# M242A.net
KiCad netlist of a schematic drawn in EAGLE
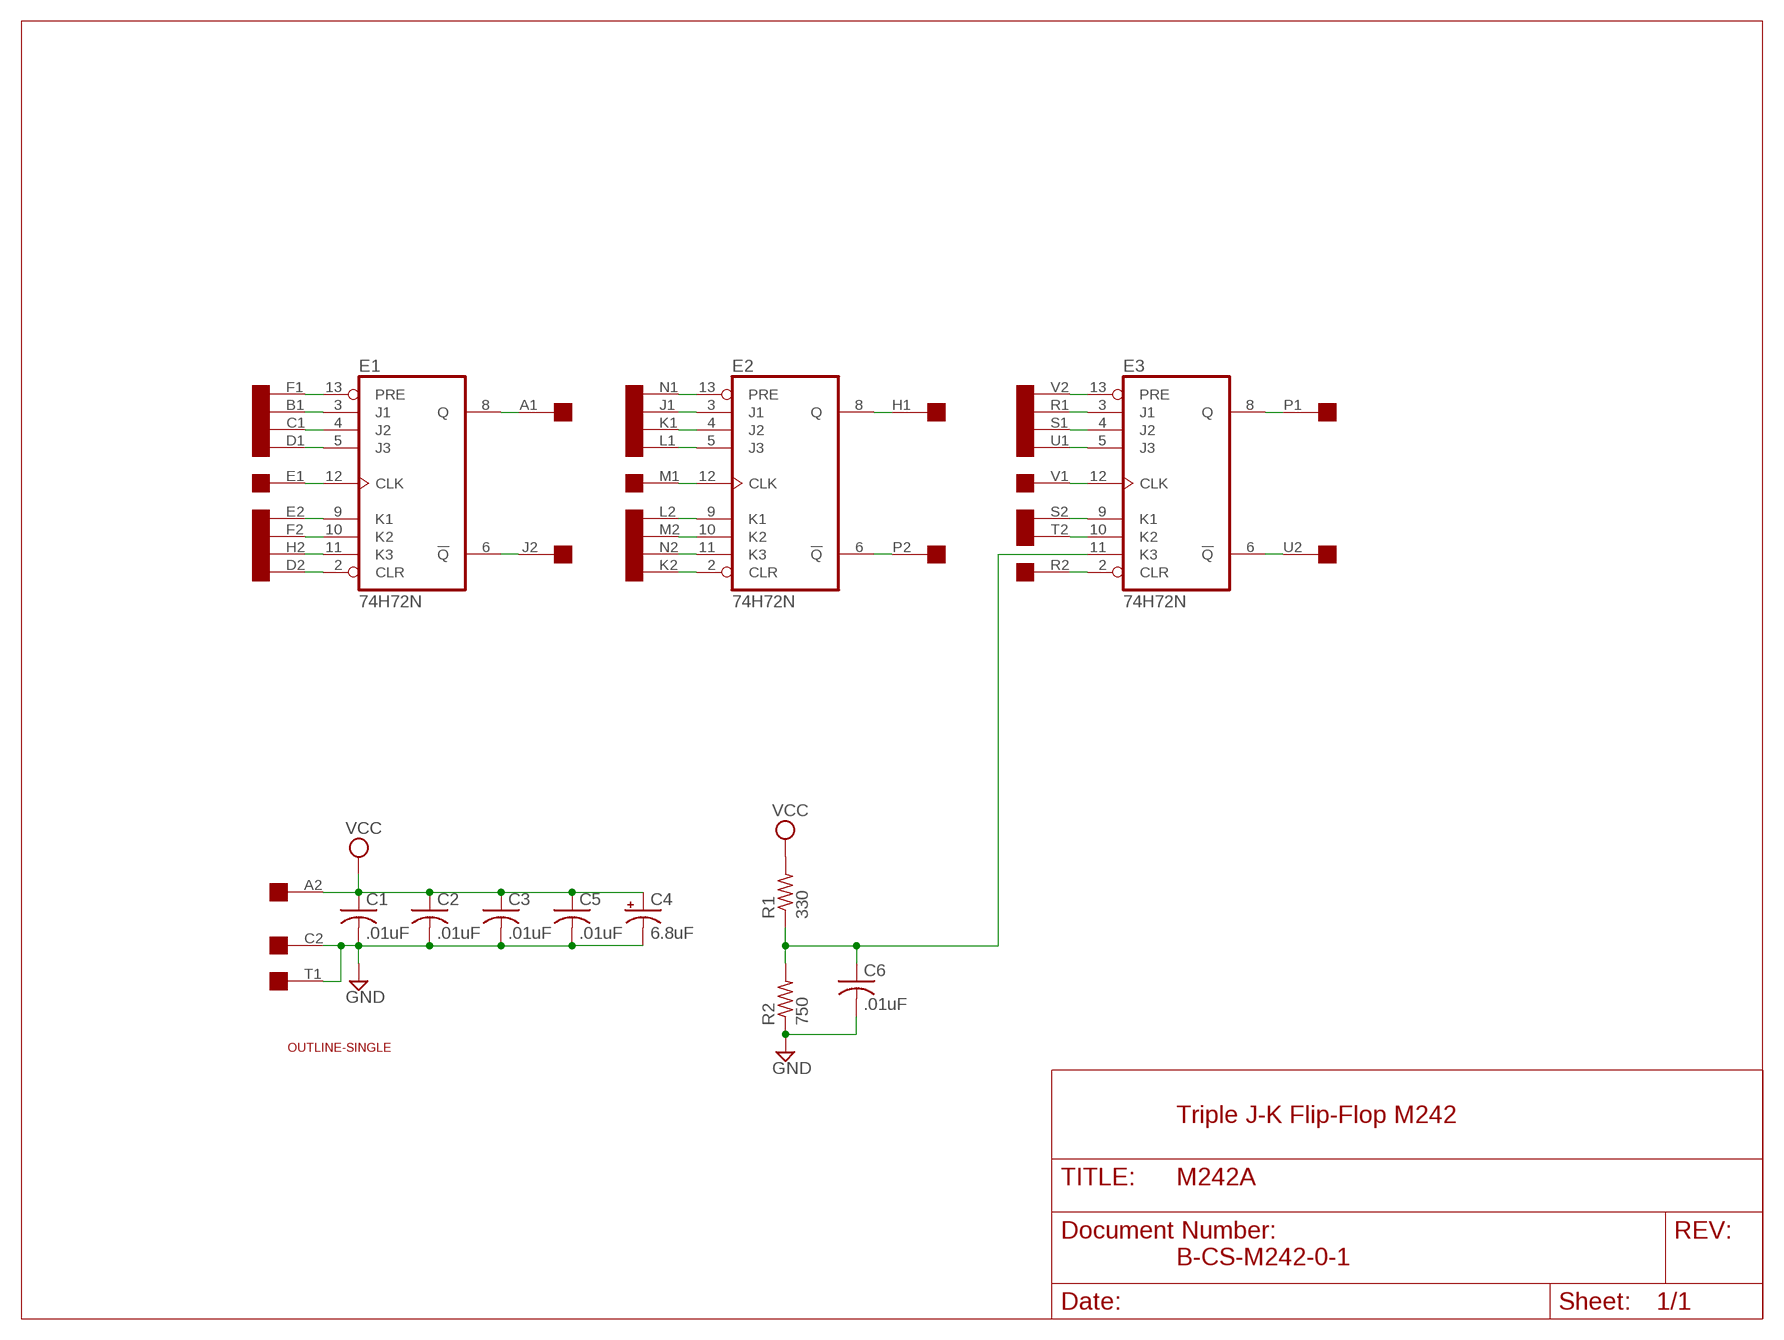
[diagram p0: schematic, sheet 1]

(export (version "E")
  (design (tool "Eeschema 10.0.6"))
  (components
    (comp (ref "C1")
      (value ".01uF")
      (footprint "eagle-import:C050-025X075")
      (libsource (lib "eagle-import") (part "C-US050-025X075"))
    )
    (comp (ref "C2")
      (value ".01uF")
      (footprint "eagle-import:C050-025X075")
      (libsource (lib "eagle-import") (part "C-US050-025X075"))
    )
    (comp (ref "C3")
      (value ".01uF")
      (footprint "eagle-import:C050-025X075")
      (libsource (lib "eagle-import") (part "C-US050-025X075"))
    )
    (comp (ref "C4")
      (value "6.8uF")
      (footprint "eagle-import:E12-8")
      (libsource (lib "eagle-import") (part "CPOL-USE20-8AXIAL"))
    )
    (comp (ref "C5")
      (value ".01uF")
      (footprint "eagle-import:C050-025X075")
      (libsource (lib "eagle-import") (part "C-US050-025X075"))
    )
    (comp (ref "C6")
      (value ".01uF")
      (footprint "eagle-import:C050-025X075")
      (libsource (lib "eagle-import") (part "C-US050-025X075"))
    )
    (comp (ref "E1")
      (value "74H72N")
      (footprint "eagle-import:DIL14")
      (libsource (lib "eagle-import") (part "7472N"))
    )
    (comp (ref "E2")
      (value "74H72N")
      (footprint "eagle-import:DIL14")
      (libsource (lib "eagle-import") (part "7472N"))
    )
    (comp (ref "E3")
      (value "74H72N")
      (footprint "eagle-import:DIL14")
      (libsource (lib "eagle-import") (part "7472N"))
    )
    (comp (ref "R1")
      (value "330")
      (footprint "eagle-import:0207_10")
      (libsource (lib "eagle-import") (part "R-US_0207/10"))
    )
    (comp (ref "R2")
      (value "750")
      (footprint "eagle-import:0207_10")
      (libsource (lib "eagle-import") (part "R-US_0207/10"))
    )
    (comp (ref "U$1")
      (value "OUTLINE-SINGLE")
      (footprint "eagle-import:SINGLE")
      (libsource (lib "eagle-import") (part "OUTLINE-SINGLE"))
    )
    (comp (ref "U$2")
      (value "SINGLE")
      (footprint "eagle-import:EDGE-CON2")
      (libsource (lib "eagle-import") (part "SINGLE"))
    )
  )
  (nets
    (net (code "1") (name "GND") (class "Default")
      (node (ref "C1") (pin "2") (pinfunction "2_2") (pintype "passive"))
      (node (ref "C2") (pin "2") (pinfunction "2_2") (pintype "passive"))
      (node (ref "C3") (pin "2") (pinfunction "2_2") (pintype "passive"))
      (node (ref "C4") (pin "-") (pinfunction "-_-") (pintype "passive"))
      (node (ref "C5") (pin "2") (pinfunction "2_2") (pintype "passive"))
      (node (ref "C6") (pin "2") (pinfunction "2_2") (pintype "passive"))
      (node (ref "R2") (pin "1") (pinfunction "1_1") (pintype "passive"))
      (node (ref "U$2") (pin "C2") (pinfunction "1_C2") (pintype "bidirectional"))
      (node (ref "U$2") (pin "T1") (pinfunction "1_T1") (pintype "bidirectional"))
    )
    (net (code "2") (name "Net-(E1A-CLK)") (class "Default")
      (node (ref "E1") (pin "12") (pinfunction "CLK_12") (pintype "input"))
      (node (ref "U$2") (pin "E1") (pinfunction "1_E1") (pintype "bidirectional"))
    )
    (net (code "3") (name "Net-(E1A-CLR)") (class "Default")
      (node (ref "E1") (pin "2") (pinfunction "CLR_2") (pintype "input"))
      (node (ref "U$2") (pin "D2") (pinfunction "1_D2") (pintype "bidirectional"))
    )
    (net (code "4") (name "Net-(E1A-J1)") (class "Default")
      (node (ref "E1") (pin "3") (pinfunction "J1_3") (pintype "input"))
      (node (ref "U$2") (pin "B1") (pinfunction "1_B1") (pintype "bidirectional"))
    )
    (net (code "5") (name "Net-(E1A-J2)") (class "Default")
      (node (ref "E1") (pin "4") (pinfunction "J2_4") (pintype "input"))
      (node (ref "U$2") (pin "C1") (pinfunction "1_C1") (pintype "bidirectional"))
    )
    (net (code "6") (name "Net-(E1A-J3)") (class "Default")
      (node (ref "E1") (pin "5") (pinfunction "J3_5") (pintype "input"))
      (node (ref "U$2") (pin "D1") (pinfunction "1_D1") (pintype "bidirectional"))
    )
    (net (code "7") (name "Net-(E1A-K1)") (class "Default")
      (node (ref "E1") (pin "9") (pinfunction "K1_9") (pintype "input"))
      (node (ref "U$2") (pin "E2") (pinfunction "1_E2") (pintype "bidirectional"))
    )
    (net (code "8") (name "Net-(E1A-K2)") (class "Default")
      (node (ref "E1") (pin "10") (pinfunction "K2_10") (pintype "input"))
      (node (ref "U$2") (pin "F2") (pinfunction "1_F2") (pintype "bidirectional"))
    )
    (net (code "9") (name "Net-(E1A-K3)") (class "Default")
      (node (ref "E1") (pin "11") (pinfunction "K3_11") (pintype "input"))
      (node (ref "U$2") (pin "H2") (pinfunction "1_H2") (pintype "bidirectional"))
    )
    (net (code "10") (name "Net-(E1A-PRE)") (class "Default")
      (node (ref "E1") (pin "13") (pinfunction "PRE_13") (pintype "input"))
      (node (ref "U$2") (pin "F1") (pinfunction "1_F1") (pintype "bidirectional"))
    )
    (net (code "11") (name "Net-(E1A-Q)") (class "Default")
      (node (ref "E1") (pin "8") (pinfunction "Q_8") (pintype "output"))
      (node (ref "U$2") (pin "A1") (pinfunction "1_A1") (pintype "bidirectional"))
    )
    (net (code "12") (name "Net-(E1A-~{Q})") (class "Default")
      (node (ref "E1") (pin "6") (pinfunction "~{Q}_6") (pintype "output"))
      (node (ref "U$2") (pin "J2") (pinfunction "1_J2") (pintype "bidirectional"))
    )
    (net (code "13") (name "Net-(E2A-CLK)") (class "Default")
      (node (ref "E2") (pin "12") (pinfunction "CLK_12") (pintype "input"))
      (node (ref "U$2") (pin "M1") (pinfunction "1_M1") (pintype "bidirectional"))
    )
    (net (code "14") (name "Net-(E2A-CLR)") (class "Default")
      (node (ref "E2") (pin "2") (pinfunction "CLR_2") (pintype "input"))
      (node (ref "U$2") (pin "K2") (pinfunction "1_K2") (pintype "bidirectional"))
    )
    (net (code "15") (name "Net-(E2A-J1)") (class "Default")
      (node (ref "E2") (pin "3") (pinfunction "J1_3") (pintype "input"))
      (node (ref "U$2") (pin "J1") (pinfunction "1_J1") (pintype "bidirectional"))
    )
    (net (code "16") (name "Net-(E2A-J2)") (class "Default")
      (node (ref "E2") (pin "4") (pinfunction "J2_4") (pintype "input"))
      (node (ref "U$2") (pin "K1") (pinfunction "1_K1") (pintype "bidirectional"))
    )
    (net (code "17") (name "Net-(E2A-J3)") (class "Default")
      (node (ref "E2") (pin "5") (pinfunction "J3_5") (pintype "input"))
      (node (ref "U$2") (pin "L1") (pinfunction "1_L1") (pintype "bidirectional"))
    )
    (net (code "18") (name "Net-(E2A-K1)") (class "Default")
      (node (ref "E2") (pin "9") (pinfunction "K1_9") (pintype "input"))
      (node (ref "U$2") (pin "L2") (pinfunction "1_L2") (pintype "bidirectional"))
    )
    (net (code "19") (name "Net-(E2A-K2)") (class "Default")
      (node (ref "E2") (pin "10") (pinfunction "K2_10") (pintype "input"))
      (node (ref "U$2") (pin "M2") (pinfunction "1_M2") (pintype "bidirectional"))
    )
    (net (code "20") (name "Net-(E2A-K3)") (class "Default")
      (node (ref "E2") (pin "11") (pinfunction "K3_11") (pintype "input"))
      (node (ref "U$2") (pin "N2") (pinfunction "1_N2") (pintype "bidirectional"))
    )
    (net (code "21") (name "Net-(E2A-PRE)") (class "Default")
      (node (ref "E2") (pin "13") (pinfunction "PRE_13") (pintype "input"))
      (node (ref "U$2") (pin "N1") (pinfunction "1_N1") (pintype "bidirectional"))
    )
    (net (code "22") (name "Net-(E2A-Q)") (class "Default")
      (node (ref "E2") (pin "8") (pinfunction "Q_8") (pintype "output"))
      (node (ref "U$2") (pin "H1") (pinfunction "1_H1") (pintype "bidirectional"))
    )
    (net (code "23") (name "Net-(E2A-~{Q})") (class "Default")
      (node (ref "E2") (pin "6") (pinfunction "~{Q}_6") (pintype "output"))
      (node (ref "U$2") (pin "P2") (pinfunction "1_P2") (pintype "bidirectional"))
    )
    (net (code "24") (name "Net-(E3A-CLK)") (class "Default")
      (node (ref "E3") (pin "12") (pinfunction "CLK_12") (pintype "input"))
      (node (ref "U$2") (pin "V1") (pinfunction "1_V1") (pintype "bidirectional"))
    )
    (net (code "25") (name "Net-(E3A-CLR)") (class "Default")
      (node (ref "E3") (pin "2") (pinfunction "CLR_2") (pintype "input"))
      (node (ref "U$2") (pin "R2") (pinfunction "1_R2") (pintype "bidirectional"))
    )
    (net (code "26") (name "Net-(E3A-J1)") (class "Default")
      (node (ref "E3") (pin "3") (pinfunction "J1_3") (pintype "input"))
      (node (ref "U$2") (pin "R1") (pinfunction "1_R1") (pintype "bidirectional"))
    )
    (net (code "27") (name "Net-(E3A-J2)") (class "Default")
      (node (ref "E3") (pin "4") (pinfunction "J2_4") (pintype "input"))
      (node (ref "U$2") (pin "S1") (pinfunction "1_S1") (pintype "bidirectional"))
    )
    (net (code "28") (name "Net-(E3A-J3)") (class "Default")
      (node (ref "E3") (pin "5") (pinfunction "J3_5") (pintype "input"))
      (node (ref "U$2") (pin "U1") (pinfunction "1_U1") (pintype "bidirectional"))
    )
    (net (code "29") (name "Net-(E3A-K1)") (class "Default")
      (node (ref "E3") (pin "9") (pinfunction "K1_9") (pintype "input"))
      (node (ref "U$2") (pin "S2") (pinfunction "1_S2") (pintype "bidirectional"))
    )
    (net (code "30") (name "Net-(E3A-K2)") (class "Default")
      (node (ref "E3") (pin "10") (pinfunction "K2_10") (pintype "input"))
      (node (ref "U$2") (pin "T2") (pinfunction "1_T2") (pintype "bidirectional"))
    )
    (net (code "31") (name "Net-(E3A-K3)") (class "Default")
      (node (ref "C6") (pin "1") (pinfunction "1_1") (pintype "passive"))
      (node (ref "E3") (pin "11") (pinfunction "K3_11") (pintype "input"))
      (node (ref "R1") (pin "1") (pinfunction "1_1") (pintype "passive"))
      (node (ref "R2") (pin "2") (pinfunction "2_2") (pintype "passive"))
    )
    (net (code "32") (name "Net-(E3A-PRE)") (class "Default")
      (node (ref "E3") (pin "13") (pinfunction "PRE_13") (pintype "input"))
      (node (ref "U$2") (pin "V2") (pinfunction "1_V2") (pintype "bidirectional"))
    )
    (net (code "33") (name "Net-(E3A-Q)") (class "Default")
      (node (ref "E3") (pin "8") (pinfunction "Q_8") (pintype "output"))
      (node (ref "U$2") (pin "P1") (pinfunction "1_P1") (pintype "bidirectional"))
    )
    (net (code "34") (name "Net-(E3A-~{Q})") (class "Default")
      (node (ref "E3") (pin "6") (pinfunction "~{Q}_6") (pintype "output"))
      (node (ref "U$2") (pin "U2") (pinfunction "1_U2") (pintype "bidirectional"))
    )
    (net (code "35") (name "VCC") (class "Default")
      (node (ref "C1") (pin "1") (pinfunction "1_1") (pintype "passive"))
      (node (ref "C2") (pin "1") (pinfunction "1_1") (pintype "passive"))
      (node (ref "C3") (pin "1") (pinfunction "1_1") (pintype "passive"))
      (node (ref "C4") (pin "+") (pinfunction "+_+") (pintype "passive"))
      (node (ref "C5") (pin "1") (pinfunction "1_1") (pintype "passive"))
      (node (ref "R1") (pin "2") (pinfunction "2_2") (pintype "passive"))
      (node (ref "U$2") (pin "A2") (pinfunction "1_A2") (pintype "bidirectional"))
    )
  )
)
